# BMS_Current_Sense.net
KiCad netlist of a schematic drawn in Altium Designer
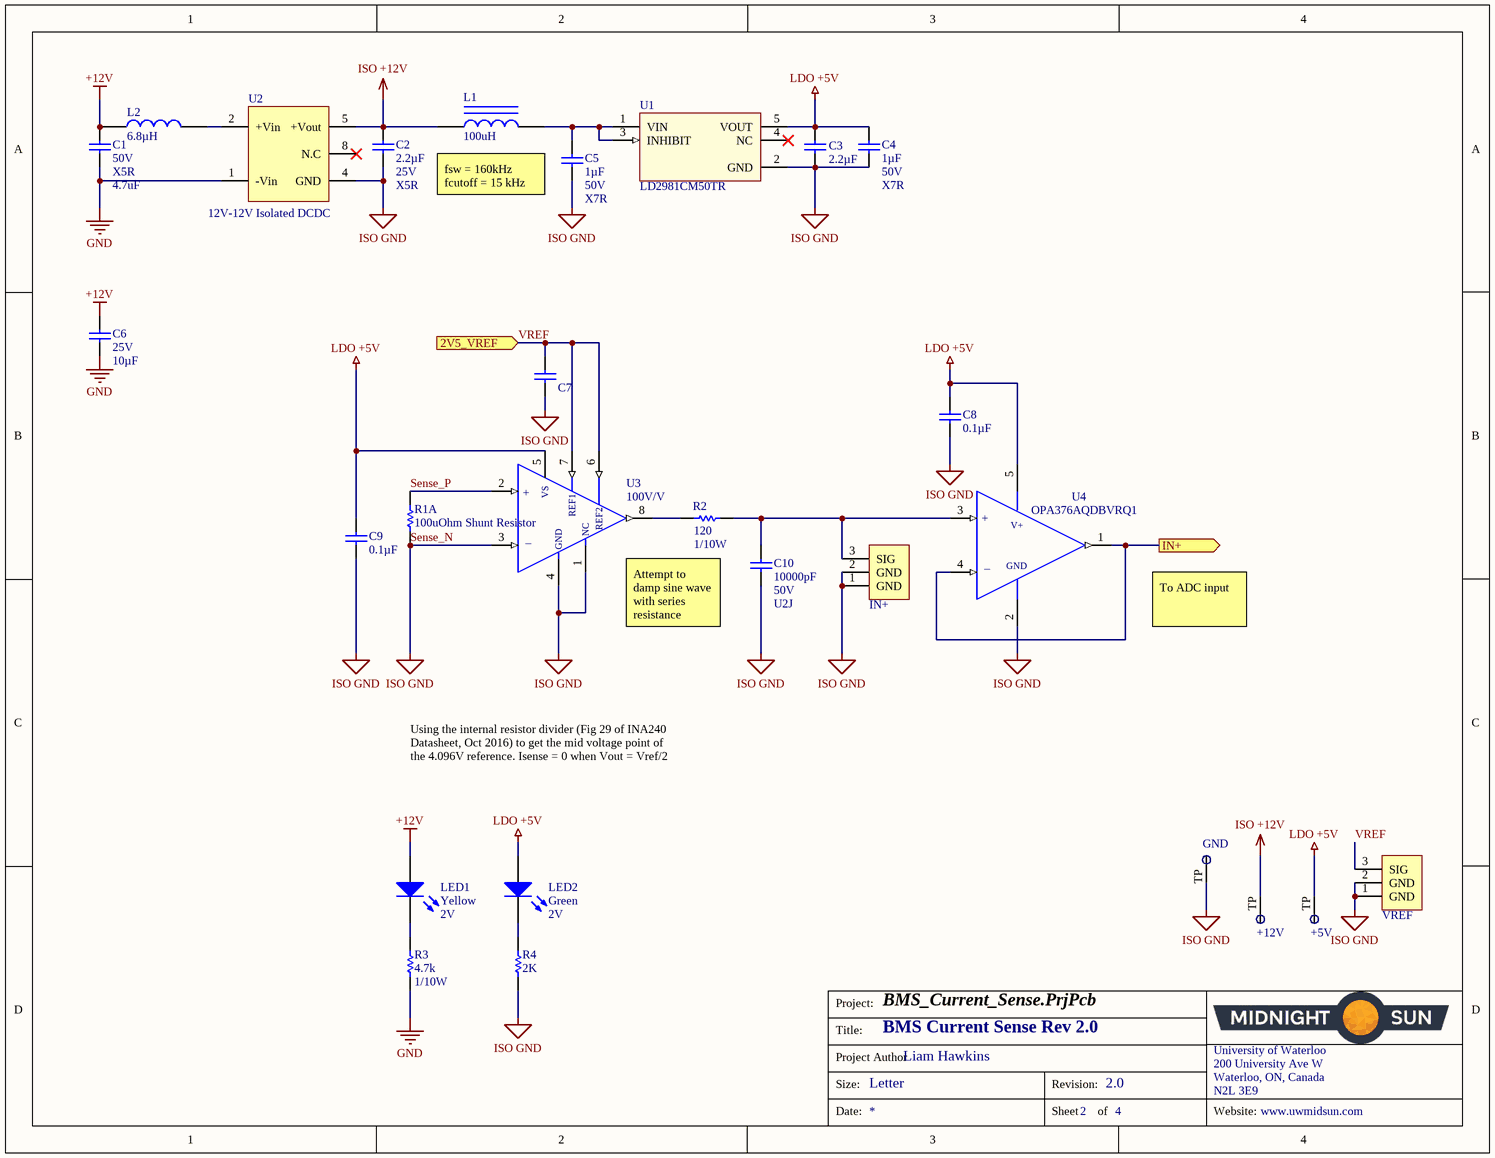
[diagram p0: BMS_Current_Sense.SchDoc]

(export (version "E")
  (design (tool "Eeschema 10.0.6"))
  (components
    (comp (ref "+5V")
      (value "Test Point")
      (footprint "Test Point")
      (libsource (lib "Schematic Diagrams") (part "Test Point"))
    )
    (comp (ref "+12V")
      (value "Test Point")
      (footprint "Test Point")
      (libsource (lib "Schematic Diagrams") (part "Test Point"))
    )
    (comp (ref "C1")
      (value "4.7uF")
      (footprint "CAP, 0805")
      (description "4.7µF ±20% 50V Ceramic Capacitor X5R 0805 (2012 Metric)")
      (fields
        (field (name "TOLERANCE") "±20%")
        (field (name "VOLTAGE - RATED") "50V")
        (field (name "TEMPERATURE COEFFICIENT") "X5R")
        (field (name "Comment") "CAP CER 4.7UF 50V 10% X5R 0805")
      )
      (libsource (lib "Schematic Diagrams") (part "CAP CER 4.7UF 50V 10% X5R 0805"))
    )
    (comp (ref "C2")
      (value "CAP CER 2.2UF 25V 10% X5R 0603")
      (footprint "CAP, 0603")
      (description "2.2µF ±10% 25V Ceramic Capacitor X5R 0603 (1608 Metric)")
      (fields
        (field (name "TOLERANCE") "±10%")
        (field (name "CAPACITANCE") "2.2µF")
        (field (name "VOLTAGE") "25V")
        (field (name "TEMPERATURE COEFFICIENT") "X5R")
      )
      (libsource (lib "Schematic Diagrams") (part "CAP CER 2.2UF 25V 10% X5R 0603"))
    )
    (comp (ref "C3")
      (value "CAP CER 2.2UF 25V 10% X5R 0603")
      (footprint "CAP, 0603")
      (description "2.2µF ±10% 25V Ceramic Capacitor X5R 0603 (1608 Metric)")
      (fields
        (field (name "TOLERANCE") "±10%")
        (field (name "CAPACITANCE") "2.2µF")
        (field (name "VOLTAGE") "25V")
      )
      (libsource (lib "Schematic Diagrams") (part "CAP CER 2.2UF 25V 10% X5R 0603"))
    )
    (comp (ref "C4")
      (value "CAP CER 1UF 50V 10% X7R 0603")
      (footprint "CAP, 0603")
      (description "1µF ±10% 50V Ceramic Capacitor X7R 0603 (1608 Metric)")
      (fields
        (field (name "TOLERANCE") "±10%")
        (field (name "CAPACITANCE") "1µF")
        (field (name "VOLTAGE") "50V")
        (field (name "TEMPERATURE COEFFICIENT") "X7R")
      )
      (libsource (lib "Schematic Diagrams") (part "CAP CER 1UF 50V 10% X7R 0603"))
    )
    (comp (ref "C5")
      (value "CAP CER 1UF 50V 10% X7R 0603")
      (footprint "CAP, 0603")
      (description "1µF ±10% 50V Ceramic Capacitor X7R 0603 (1608 Metric)")
      (fields
        (field (name "TOLERANCE") "±10%")
        (field (name "CAPACITANCE") "1µF")
        (field (name "VOLTAGE") "50V")
        (field (name "TEMPERATURE COEFFICIENT") "X7R")
      )
      (libsource (lib "Schematic Diagrams") (part "CAP CER 1UF 50V 10% X7R 0603"))
    )
    (comp (ref "C6")
      (value "CAP CER 10uF 25V 10% X5R 0805")
      (footprint "CAP, 0805")
      (description "10µF ±10% 25V Ceramic Capacitor X5R 0805 (2012 Metric)")
      (fields
        (field (name "MANUFACTURER") "Murata Electronics North America")
        (field (name "MANUFACTURER PART NUMBER") "GRM21BR61E106KA73L")
        (field (name "VOLTAGE - RATED") "25V")
        (field (name "CAPACITANCE") "10µF")
      )
      (libsource (lib "Schematic Diagrams") (part "CAP CER 10uF 25V 10% X5R 0805"))
    )
    (comp (ref "C7")
      (value "CAP CER 0.022UF 50V 10% X7R 0603")
      (footprint "CAP, 0603")
      (description "0.022µF ±10% 50V Ceramic Capacitor X7R 0603 (1608 Metric)")
      (fields (field (name "TOLERANCE") "±10%"))
      (libsource (lib "Schematic Diagrams") (part "CAP CER 0.022UF 50V 10% X7R 0603"))
    )
    (comp (ref "C8")
      (value "CAP CER 0.1UF 50V 10% X7R 0603")
      (footprint "CAP, 0603")
      (description "0.10µF ±10% 50V Ceramic Capacitor X7R 0603 (1608 Metric)")
      (fields
        (field (name "TOLERANCE") "±10%")
        (field (name "CAPACITANCE") "0.1µF")
        (field (name "VOLTAGE") "50V")
      )
      (libsource (lib "Schematic Diagrams") (part "CAP CER 0.1UF 50V 10% X7R 0603"))
    )
    (comp (ref "C9")
      (value "CAP CER 0.1UF 50V 10% X7R 0603")
      (footprint "CAP, 0603")
      (description "0.10µF ±10% 50V Ceramic Capacitor X7R 0603 (1608 Metric)")
      (fields
        (field (name "TOLERANCE") "±10%")
        (field (name "CAPACITANCE") "0.1µF")
        (field (name "VOLTAGE") "50V")
      )
      (libsource (lib "Schematic Diagrams") (part "CAP CER 0.1UF 50V 10% X7R 0603"))
    )
    (comp (ref "C10")
      (value "CAP CER 10nF 50V 5% X7R 0603")
      (footprint "CAP, 0603")
      (description "10000pF ±5% 50V Ceramic Capacitor U2J 0603 (1608 Metric)")
      (fields
        (field (name "TOLERANCE") "±5%")
        (field (name "CAPACITANCE") "10000pF")
        (field (name "VOLTAGE") "50V")
        (field (name "TEMPERATURE COEFFICIENT") "U2J")
      )
      (libsource (lib "Schematic Diagrams") (part "CAP CER 10nF 50V 5% X7R 0603"))
    )
    (comp (ref "GND")
      (value "Test Point")
      (footprint "Test Point")
      (libsource (lib "Schematic Diagrams") (part "Test Point"))
    )
    (comp (ref "IN+")
      (value "U.FL-R-SMT-1(01)")
      (footprint "CONN U.FL RCPT STR 50 OHM SMD")
      (description "U.FL (UMCC) Connector Receptacle, Male Pin 50Ohm Surface Mount Solder")
      (fields (field (name "MANUFACTURER") "Hirose"))
      (libsource (lib "Schematic Diagrams") (part "CONN U.FL RCPT STR 50 OHM SMD"))
    )
    (comp (ref "L1")
      (value "100uH")
      (footprint "1210")
      (description "100µH Unshielded Wirewound Inductor 60mA 11 Ohm Max 1210 (3225 Metric)")
      (fields
        (field (name "MANUFACTURER") "EPCOS (TDK)")
        (field (name "MANUFACTURER PART NUMBER") "B82422T1104J000")
      )
      (libsource (lib "Schematic Diagrams") (part "IND 100uH 60mA 5% 1210"))
    )
    (comp (ref "L2")
      (value "IND 6.8uH 260mA 20% 1210")
      (footprint "NLFV32T-6R8M-EF/IND 6.8uH")
      (description "6.8µH Shielded Wirewound Inductor 260mA 204 mOhm Max 1210 (3225 Metric)")
      (fields (field (name "TOLERANCE") "±20%") (field (name "INDUCTANCE") "6.8µH"))
      (libsource (lib "Schematic Diagrams") (part "IND 6.8uH 260mA 20% 1210"))
    )
    (comp (ref "LED1")
      (value "LED YELLOW CLEAR 2.1V 0603")
      (footprint "LED_0603")
      (description "Yellow 590nm LED Indication - Discrete 2V 0603 (1608 Metric)")
      (fields
        (field (name "MANUFACTURER") "Wurth Electronics Inc.")
        (field (name "MANUFACTURER PART NUMBER") "150060YS75000")
        (field (name "COLOR") "Yellow")
        (field (name "VOLTAGE - FORWARD (VF) (TYP)") "2V")
      )
      (libsource (lib "Schematic Diagrams") (part "LED YELLOW CLEAR 2.1V 0603"))
    )
    (comp (ref "LED2")
      (value "LED GREEN CLEAR 2V 0603")
      (footprint "LED_0603")
      (description "Green 572nm LED Indication - Discrete 2V 0603 (1608 Metric)")
      (fields
        (field (name "MANUFACTURER") "Wurth Electronics Inc.")
        (field (name "MANUFACTURER PART NUMBER") "150060VS75000")
        (field (name "COLOR") "Green")
        (field (name "VOLTAGE - FORWARD (VF) (TYP)") "2V")
      )
      (libsource (lib "Schematic Diagrams") (part "LED GREEN CLEAR 2V 0603"))
    )
    (comp (ref "R1")
      (value "100uOhm Shunt Resistor")
      (footprint "RES SHUNT 100UOHM 60MM")
      (fields (field (name "TOLERANCE") "±5%"))
      (libsource (lib "Schematic Diagrams") (part "RES SHUNT 100UOHM 5% 36W 60MM"))
    )
    (comp (ref "R2")
      (value "RES 120 OHM 1% 1/10W 0603")
      (footprint "RES, 0603")
      (description "RES SMD 120 OHM 1% 1/10W 0603")
      (fields
        (field (name "TOLERANCE") "±1%")
        (field (name "RESISTANCE") "120")
        (field (name "POWER") "1/10W")
      )
      (libsource (lib "Schematic Diagrams") (part "RES 120 OHM 1% 1/10W 0603"))
    )
    (comp (ref "R3")
      (value "RES 4.7K OHM 1% 1/10W 0603")
      (footprint "RES, 0603")
      (description "4.7k Ohm ±1% 0.1W, 1/10W Chip Resistor 0603 (1608 Metric) Moisture Resistant Thick Film")
      (fields
        (field (name "TOLERANCE") "±1%")
        (field (name "RESISTANCE (OHMS)") "4.7k")
        (field (name "POWER (WATTS)") "1/10W")
      )
      (libsource (lib "Schematic Diagrams") (part "RES 4.7K OHM 1% 1/10W 0603"))
    )
    (comp (ref "R4")
      (value "2K")
      (footprint "RES, 0603")
      (description "2k Ohm ±1% 0.1W, 1/10W Chip Resistor 0603 (1608 Metric) Moisture Resistant Thick Film")
      (fields
        (field (name "MANUFACTURER") "Yageo")
        (field (name "MANUFACTURER PART NUMBER") "RC0603FR-072KL")
      )
      (libsource (lib "Schematic Diagrams") (part "RES 2K OHM 1% 1/10W 0603"))
    )
    (comp (ref "U1")
      (value "IC REG LDO 5V 0.1A SOT23-5")
      (footprint "SOT95P280X145-5N")
      (description "Linear Voltage Regulator IC Positive Fixed Output 5V 100mA SOT-23-5")
      (fields (field (name "MANUFACTURER PART NUMBER 1") "LD2981CM50TR"))
      (libsource (lib "Schematic Diagrams") (part "IC REG LDO 5V 0.1A SOT23-5"))
    )
    (comp (ref "U2")
      (value "IC DCDC ISOLATED 12V 1W 8-SMD 5-LEAD")
      (footprint "IC, Isolated DCDC")
      (description "Isolated Module DC DC Converter 1 Output 12V 84mA 10.8V - 13.2V Input")
      (fields (field (name "POWER") "1W") (field (name "TYPE") "12V-12V Isolated DCDC"))
      (libsource (lib "Schematic Diagrams") (part "IC DCDC ISOLATED 12V 1W 8-SMD 5-LEAD"))
    )
    (comp (ref "U3")
      (value "100V/V")
      (footprint "IC CURRENT AMPLIFIER INA240 TSSOP-8")
      (description "Current Sense Amplifier 1 Circuit 8-TSSOP")
      (libsource (lib "Schematic Diagrams") (part "IC CURRENT AMPLIFIER INA240 8-TSSOP"))
    )
    (comp (ref "U4")
      (value "IC OP AMP GEN PURPOSE RR 5.5MHZ SOT-23-5")
      (footprint "IC OP AMP GP RR 10MHZ SOT-23-5")
      (description "General Purpose Amplifier 1 Circuit Rail-to-Rail SOT-23-5")
      (fields
        (field (name "MANUFACTURER") "Texas Instruments")
        (field (name "MANUFACTURER PART NUMBER") "OPA376AQDBVRQ1")
      )
      (libsource (lib "Schematic Diagrams") (part "IC OP AMP GEN PURPOSE RR 5.5MHZ SOT-23-5"))
    )
    (comp (ref "VREF")
      (value "U.FL-R-SMT-1(01)")
      (footprint "CONN U.FL RCPT STR 50 OHM SMD")
      (description "U.FL (UMCC) Connector Receptacle, Male Pin 50Ohm Surface Mount Solder")
      (fields (field (name "MANUFACTURER") "Hirose"))
      (libsource (lib "Schematic Diagrams") (part "CONN U.FL RCPT STR 50 OHM SMD"))
    )
  )
  (nets
    (net (code "1") (name "+12V") (class "Default")
      (node (ref "C1") (pin "1") (pinfunction "1_1") (pintype "passive"))
      (node (ref "C6") (pin "1") (pinfunction "1_1") (pintype "passive"))
      (node (ref "L2") (pin "1") (pinfunction "1_1") (pintype "passive"))
      (node (ref "LED1") (pin "1") (pinfunction "A_1") (pintype "passive"))
    )
    (net (code "2") (name "/IN+") (class "Default")
      (node (ref "U4") (pin "1") (pinfunction "OUTPUT_1") (pintype "output"))
      (node (ref "U4") (pin "4") (pinfunction "-IN_4") (pintype "input"))
    )
    (net (code "3") (name "/Sense_P") (class "Default")
      (node (ref "R1") (pin "5") (pinfunction "5_5") (pintype "passive"))
      (node (ref "U3") (pin "2") (pinfunction "+IN_2") (pintype "input"))
    )
    (net (code "4") (name "/VREF") (class "Default")
      (node (ref "C7") (pin "1") (pinfunction "1_1") (pintype "passive"))
      (node (ref "U3") (pin "6") (pinfunction "REF2_6") (pintype "input"))
      (node (ref "U3") (pin "7") (pinfunction "REF1_7") (pintype "input"))
      (node (ref "VREF") (pin "3") (pinfunction "SIG_3") (pintype "passive"))
    )
    (net (code "5") (name "GND") (class "Default")
      (node (ref "C1") (pin "2") (pinfunction "2_2") (pintype "passive"))
      (node (ref "C6") (pin "2") (pinfunction "2_2") (pintype "passive"))
      (node (ref "R3") (pin "2") (pinfunction "2_2") (pintype "passive"))
      (node (ref "U2") (pin "1") (pinfunction "-Vin_1") (pintype "passive"))
    )
    (net (code "6") (name "ISO +12V") (class "Default")
      (node (ref "+12V") (pin "TP") (pinfunction "1_TP") (pintype "passive"))
      (node (ref "C2") (pin "1") (pinfunction "1_1") (pintype "passive"))
      (node (ref "L1") (pin "1") (pinfunction "1_1") (pintype "passive"))
      (node (ref "U2") (pin "5") (pinfunction "+Vout_5") (pintype "passive"))
    )
    (net (code "7") (name "ISO GND") (class "Default")
      (node (ref "C10") (pin "2") (pinfunction "2_2") (pintype "passive"))
      (node (ref "C2") (pin "2") (pinfunction "2_2") (pintype "passive"))
      (node (ref "C3") (pin "2") (pinfunction "2_2") (pintype "passive"))
      (node (ref "C4") (pin "2") (pinfunction "2_2") (pintype "passive"))
      (node (ref "C5") (pin "2") (pinfunction "2_2") (pintype "passive"))
      (node (ref "C7") (pin "2") (pinfunction "2_2") (pintype "passive"))
      (node (ref "C8") (pin "2") (pinfunction "2_2") (pintype "passive"))
      (node (ref "C9") (pin "2") (pinfunction "2_2") (pintype "passive"))
      (node (ref "GND") (pin "TP") (pinfunction "1_TP") (pintype "passive"))
      (node (ref "IN+") (pin "1") (pinfunction "GND_1") (pintype "passive"))
      (node (ref "IN+") (pin "2") (pinfunction "GND_2") (pintype "passive"))
      (node (ref "R1") (pin "6") (pinfunction "6_6") (pintype "passive"))
      (node (ref "R4") (pin "2") (pinfunction "2_2") (pintype "passive"))
      (node (ref "U1") (pin "2") (pinfunction "GND_2") (pintype "power_in"))
      (node (ref "U2") (pin "4") (pinfunction "GND_4") (pintype "passive"))
      (node (ref "U3") (pin "1") (pinfunction "NC_1") (pintype "power_in"))
      (node (ref "U3") (pin "3") (pinfunction "-IN_3") (pintype "input"))
      (node (ref "U3") (pin "4") (pinfunction "GND_4") (pintype "power_in"))
      (node (ref "U4") (pin "2") (pinfunction "VSS_2") (pintype "power_in"))
      (node (ref "VREF") (pin "1") (pinfunction "GND_1") (pintype "passive"))
      (node (ref "VREF") (pin "2") (pinfunction "GND_2") (pintype "passive"))
    )
    (net (code "8") (name "LDO +5V") (class "Default")
      (node (ref "+5V") (pin "TP") (pinfunction "1_TP") (pintype "passive"))
      (node (ref "C3") (pin "1") (pinfunction "1_1") (pintype "passive"))
      (node (ref "C4") (pin "1") (pinfunction "1_1") (pintype "passive"))
      (node (ref "C8") (pin "1") (pinfunction "1_1") (pintype "passive"))
      (node (ref "C9") (pin "1") (pinfunction "1_1") (pintype "passive"))
      (node (ref "LED2") (pin "1") (pinfunction "A_1") (pintype "passive"))
      (node (ref "U1") (pin "5") (pinfunction "VOUT_5") (pintype "power_in"))
      (node (ref "U3") (pin "5") (pinfunction "VS_5") (pintype "power_in"))
      (node (ref "U4") (pin "5") (pinfunction "VDD_5") (pintype "power_in"))
    )
    (net (code "9") (name "Net-(IN+-SIG)") (class "Default")
      (node (ref "C10") (pin "1") (pinfunction "1_1") (pintype "passive"))
      (node (ref "IN+") (pin "3") (pinfunction "SIG_3") (pintype "passive"))
      (node (ref "R2") (pin "2") (pinfunction "2_2") (pintype "passive"))
      (node (ref "U4") (pin "3") (pinfunction "+IN_3") (pintype "input"))
    )
    (net (code "10") (name "Net-(LED1-K)") (class "Default")
      (node (ref "LED1") (pin "2") (pinfunction "K_2") (pintype "passive"))
      (node (ref "R3") (pin "1") (pinfunction "1_1") (pintype "passive"))
    )
    (net (code "11") (name "Net-(LED2-K)") (class "Default")
      (node (ref "LED2") (pin "2") (pinfunction "K_2") (pintype "passive"))
      (node (ref "R4") (pin "1") (pinfunction "1_1") (pintype "passive"))
    )
    (net (code "12") (name "Net-(U1-INHIBIT)") (class "Default")
      (node (ref "C5") (pin "1") (pinfunction "1_1") (pintype "passive"))
      (node (ref "L1") (pin "2") (pinfunction "2_2") (pintype "passive"))
      (node (ref "U1") (pin "1") (pinfunction "VIN_1") (pintype "power_in"))
      (node (ref "U1") (pin "3") (pinfunction "INHIBIT_3") (pintype "input"))
    )
    (net (code "13") (name "Net-(U2-+Vin)") (class "Default")
      (node (ref "L2") (pin "2") (pinfunction "2_2") (pintype "passive"))
      (node (ref "U2") (pin "2") (pinfunction "+Vin_2") (pintype "passive"))
    )
    (net (code "14") (name "Net-(U3-OUTPUT)") (class "Default")
      (node (ref "R2") (pin "1") (pinfunction "1_1") (pintype "passive"))
      (node (ref "U3") (pin "8") (pinfunction "OUTPUT_8") (pintype "output"))
    )
    (net (code "15") (name "unconnected-(U1-NC-Pad4)") (class "Default")
      (node (ref "U1") (pin "4") (pinfunction "NC_4") (pintype "passive+no_connect"))
    )
    (net (code "16") (name "unconnected-(U2-N.C-Pad8)") (class "Default")
      (node (ref "U2") (pin "8") (pinfunction "N.C_8") (pintype "passive+no_connect"))
    )
  )
)
